# M159A.net
KiCad netlist of a schematic drawn in EAGLE
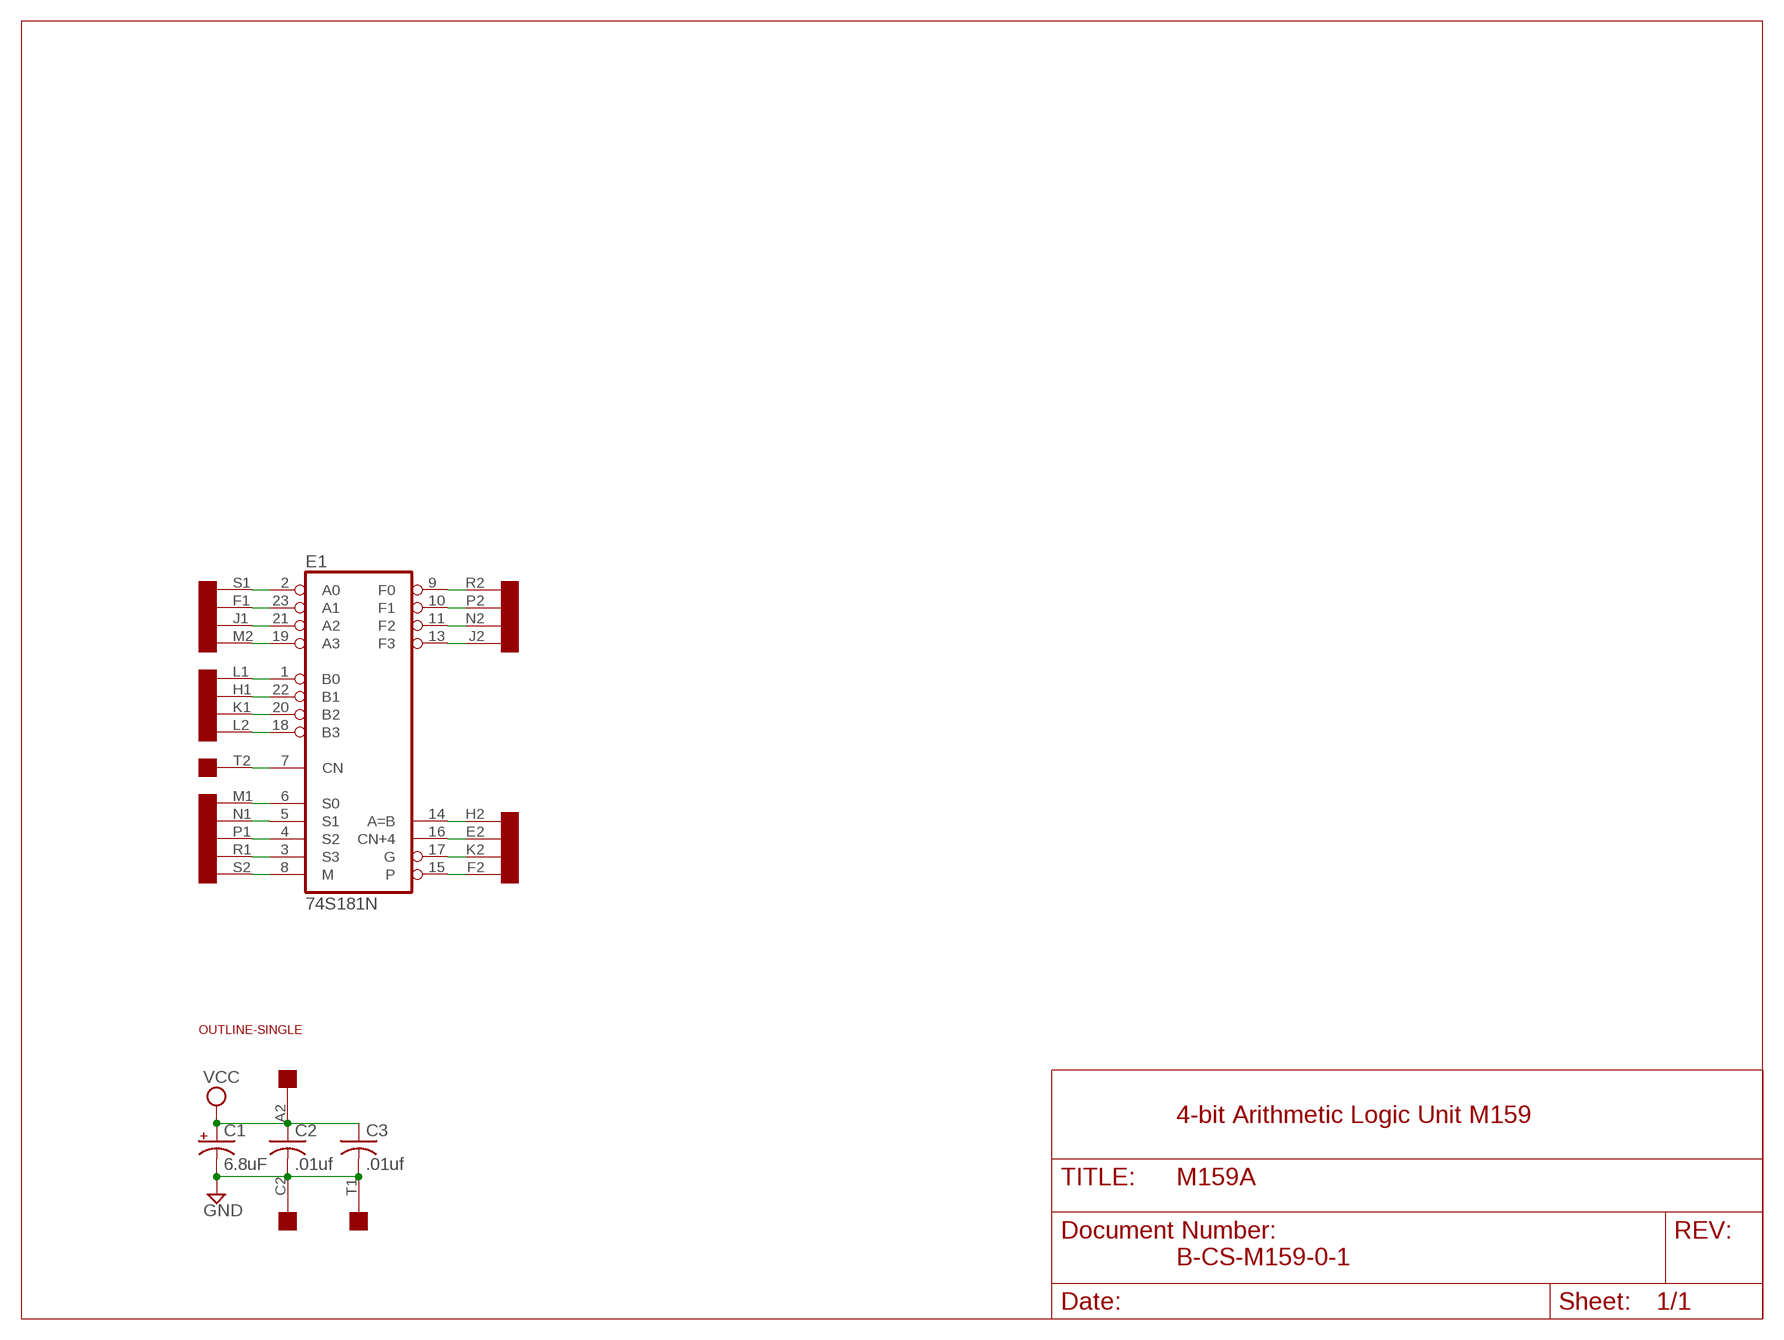
[diagram p0: schematic, sheet 1]

(export (version "E")
  (design (tool "Eeschema 10.0.6"))
  (components
    (comp (ref "C1")
      (value "6.8uF")
      (footprint "eagle-import:E22-6")
      (libsource (lib "eagle-import") (part "CPOL-USE22-6AXIAL"))
    )
    (comp (ref "C2")
      (value ".01uf")
      (footprint "eagle-import:C050-025X075")
      (libsource (lib "eagle-import") (part "C-US050-025X075"))
    )
    (comp (ref "C3")
      (value ".01uf")
      (footprint "eagle-import:C050-025X075")
      (libsource (lib "eagle-import") (part "C-US050-025X075"))
    )
    (comp (ref "E1")
      (value "74S181N")
      (footprint "eagle-import:DIL24-6")
      (libsource (lib "eagle-import") (part "74181NS"))
    )
    (comp (ref "U$1")
      (value "OUTLINE-SINGLE")
      (footprint "eagle-import:SINGLE")
      (libsource (lib "eagle-import") (part "OUTLINE-SINGLE"))
    )
    (comp (ref "U$2")
      (value "EDGE-2CONNECTOR")
      (footprint "eagle-import:EDGE-CON2")
      (libsource (lib "eagle-import") (part "EDGE-2CONNECTOR"))
    )
  )
  (nets
    (net (code "1") (name "GND") (class "Default")
      (node (ref "C1") (pin "-") (pinfunction "-_-") (pintype "passive"))
      (node (ref "C2") (pin "2") (pinfunction "2_2") (pintype "passive"))
      (node (ref "C3") (pin "2") (pinfunction "2_2") (pintype "passive"))
      (node (ref "U$2") (pin "C2") (pinfunction "1_C2") (pintype "bidirectional"))
      (node (ref "U$2") (pin "T1") (pinfunction "1_T1") (pintype "bidirectional"))
    )
    (net (code "2") (name "Net-(E1A-A0)") (class "Default")
      (node (ref "E1") (pin "2") (pinfunction "A0_2") (pintype "input"))
      (node (ref "U$2") (pin "S1") (pinfunction "1_S1") (pintype "bidirectional"))
    )
    (net (code "3") (name "Net-(E1A-A1)") (class "Default")
      (node (ref "E1") (pin "23") (pinfunction "A1_23") (pintype "input"))
      (node (ref "U$2") (pin "F1") (pinfunction "1_F1") (pintype "bidirectional"))
    )
    (net (code "4") (name "Net-(E1A-A2)") (class "Default")
      (node (ref "E1") (pin "21") (pinfunction "A2_21") (pintype "input"))
      (node (ref "U$2") (pin "J1") (pinfunction "1_J1") (pintype "bidirectional"))
    )
    (net (code "5") (name "Net-(E1A-A3)") (class "Default")
      (node (ref "E1") (pin "19") (pinfunction "A3_19") (pintype "input"))
      (node (ref "U$2") (pin "M2") (pinfunction "1_M2") (pintype "bidirectional"))
    )
    (net (code "6") (name "Net-(E1A-A=B)") (class "Default")
      (node (ref "E1") (pin "14") (pinfunction "A=B_14") (pintype "output"))
      (node (ref "U$2") (pin "H2") (pinfunction "1_H2") (pintype "bidirectional"))
    )
    (net (code "7") (name "Net-(E1A-B0)") (class "Default")
      (node (ref "E1") (pin "1") (pinfunction "B0_1") (pintype "input"))
      (node (ref "U$2") (pin "L1") (pinfunction "1_L1") (pintype "bidirectional"))
    )
    (net (code "8") (name "Net-(E1A-B1)") (class "Default")
      (node (ref "E1") (pin "22") (pinfunction "B1_22") (pintype "input"))
      (node (ref "U$2") (pin "H1") (pinfunction "1_H1") (pintype "bidirectional"))
    )
    (net (code "9") (name "Net-(E1A-B2)") (class "Default")
      (node (ref "E1") (pin "20") (pinfunction "B2_20") (pintype "input"))
      (node (ref "U$2") (pin "K1") (pinfunction "1_K1") (pintype "bidirectional"))
    )
    (net (code "10") (name "Net-(E1A-B3)") (class "Default")
      (node (ref "E1") (pin "18") (pinfunction "B3_18") (pintype "input"))
      (node (ref "U$2") (pin "L2") (pinfunction "1_L2") (pintype "bidirectional"))
    )
    (net (code "11") (name "Net-(E1A-CN)") (class "Default")
      (node (ref "E1") (pin "7") (pinfunction "CN_7") (pintype "input"))
      (node (ref "U$2") (pin "T2") (pinfunction "1_T2") (pintype "bidirectional"))
    )
    (net (code "12") (name "Net-(E1A-CN+4)") (class "Default")
      (node (ref "E1") (pin "16") (pinfunction "CN+4_16") (pintype "output"))
      (node (ref "U$2") (pin "E2") (pinfunction "1_E2") (pintype "bidirectional"))
    )
    (net (code "13") (name "Net-(E1A-F0)") (class "Default")
      (node (ref "E1") (pin "9") (pinfunction "F0_9") (pintype "output"))
      (node (ref "U$2") (pin "R2") (pinfunction "1_R2") (pintype "bidirectional"))
    )
    (net (code "14") (name "Net-(E1A-F1)") (class "Default")
      (node (ref "E1") (pin "10") (pinfunction "F1_10") (pintype "output"))
      (node (ref "U$2") (pin "P2") (pinfunction "1_P2") (pintype "bidirectional"))
    )
    (net (code "15") (name "Net-(E1A-F2)") (class "Default")
      (node (ref "E1") (pin "11") (pinfunction "F2_11") (pintype "output"))
      (node (ref "U$2") (pin "N2") (pinfunction "1_N2") (pintype "bidirectional"))
    )
    (net (code "16") (name "Net-(E1A-F3)") (class "Default")
      (node (ref "E1") (pin "13") (pinfunction "F3_13") (pintype "output"))
      (node (ref "U$2") (pin "J2") (pinfunction "1_J2") (pintype "bidirectional"))
    )
    (net (code "17") (name "Net-(E1A-G)") (class "Default")
      (node (ref "E1") (pin "17") (pinfunction "G_17") (pintype "output"))
      (node (ref "U$2") (pin "K2") (pinfunction "1_K2") (pintype "bidirectional"))
    )
    (net (code "18") (name "Net-(E1A-M)") (class "Default")
      (node (ref "E1") (pin "8") (pinfunction "M_8") (pintype "input"))
      (node (ref "U$2") (pin "S2") (pinfunction "1_S2") (pintype "bidirectional"))
    )
    (net (code "19") (name "Net-(E1A-P)") (class "Default")
      (node (ref "E1") (pin "15") (pinfunction "P_15") (pintype "output"))
      (node (ref "U$2") (pin "F2") (pinfunction "1_F2") (pintype "bidirectional"))
    )
    (net (code "20") (name "Net-(E1A-S0)") (class "Default")
      (node (ref "E1") (pin "6") (pinfunction "S0_6") (pintype "input"))
      (node (ref "U$2") (pin "M1") (pinfunction "1_M1") (pintype "bidirectional"))
    )
    (net (code "21") (name "Net-(E1A-S1)") (class "Default")
      (node (ref "E1") (pin "5") (pinfunction "S1_5") (pintype "input"))
      (node (ref "U$2") (pin "N1") (pinfunction "1_N1") (pintype "bidirectional"))
    )
    (net (code "22") (name "Net-(E1A-S2)") (class "Default")
      (node (ref "E1") (pin "4") (pinfunction "S2_4") (pintype "input"))
      (node (ref "U$2") (pin "P1") (pinfunction "1_P1") (pintype "bidirectional"))
    )
    (net (code "23") (name "Net-(E1A-S3)") (class "Default")
      (node (ref "E1") (pin "3") (pinfunction "S3_3") (pintype "input"))
      (node (ref "U$2") (pin "R1") (pinfunction "1_R1") (pintype "bidirectional"))
    )
    (net (code "24") (name "VCC") (class "Default")
      (node (ref "C1") (pin "+") (pinfunction "+_+") (pintype "passive"))
      (node (ref "C2") (pin "1") (pinfunction "1_1") (pintype "passive"))
      (node (ref "C3") (pin "1") (pinfunction "1_1") (pintype "passive"))
      (node (ref "U$2") (pin "A2") (pinfunction "1_A2") (pintype "bidirectional"))
    )
  )
)
